# Sensor_PCB.net
KiCad netlist of a schematic drawn in EAGLE
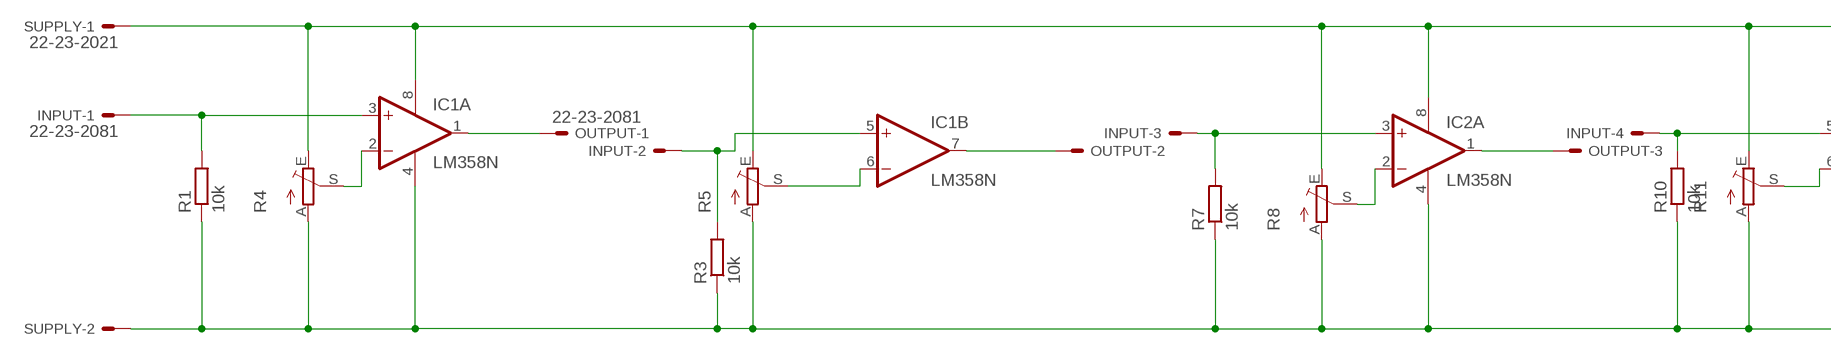
[diagram p0: schematic, sheet 1, part 1 of 2]
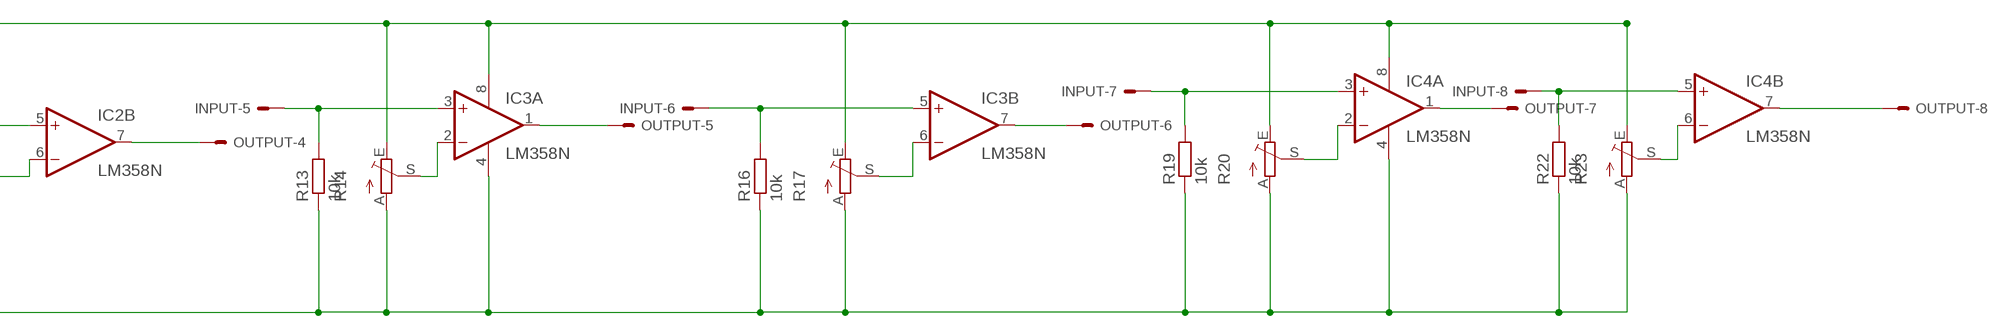
[diagram p1: schematic, sheet 1, part 2 of 2]

(export (version "E")
  (design (tool "Eeschema 10.0.6"))
  (components
    (comp (ref "IC1")
      (value "LM358N")
      (footprint "eagle-import:DIL08")
      (libsource (lib "eagle-import") (part "LM358N"))
    )
    (comp (ref "IC2")
      (value "LM358N")
      (footprint "eagle-import:DIL08")
      (libsource (lib "eagle-import") (part "LM358N"))
    )
    (comp (ref "IC3")
      (value "LM358N")
      (footprint "eagle-import:DIL08")
      (libsource (lib "eagle-import") (part "LM358N"))
    )
    (comp (ref "IC4")
      (value "LM358N")
      (footprint "eagle-import:DIL08")
      (libsource (lib "eagle-import") (part "LM358N"))
    )
    (comp (ref "INPUT")
      (value "22-23-2081")
      (footprint "eagle-import:22-23-2081")
      (fields (field (name "MF") "MOLEX"))
      (libsource (lib "eagle-import") (part "22-23-2081"))
    )
    (comp (ref "OUTPUT")
      (value "22-23-2081")
      (footprint "eagle-import:22-23-2081")
      (fields (field (name "MF") "MOLEX"))
      (libsource (lib "eagle-import") (part "22-23-2081"))
    )
    (comp (ref "R1")
      (value "10k")
      (footprint "eagle-import:R1206")
      (libsource (lib "eagle-import") (part "R-EU_R1206"))
    )
    (comp (ref "R3")
      (value "10k")
      (footprint "eagle-import:R1206")
      (libsource (lib "eagle-import") (part "R-EU_R1206"))
    )
    (comp (ref "R4")
      (value "TRIM_EU-S64Y")
      (footprint "eagle-import:S64Y")
      (libsource (lib "eagle-import") (part "TRIM_EU-S64Y"))
    )
    (comp (ref "R5")
      (value "TRIM_EU-S64Y")
      (footprint "eagle-import:S64Y")
      (libsource (lib "eagle-import") (part "TRIM_EU-S64Y"))
    )
    (comp (ref "R7")
      (value "10k")
      (footprint "eagle-import:R1206")
      (libsource (lib "eagle-import") (part "R-EU_R1206"))
    )
    (comp (ref "R8")
      (value "TRIM_EU-S64Y")
      (footprint "eagle-import:S64Y")
      (libsource (lib "eagle-import") (part "TRIM_EU-S64Y"))
    )
    (comp (ref "R10")
      (value "10k")
      (footprint "eagle-import:R1206")
      (libsource (lib "eagle-import") (part "R-EU_R1206"))
    )
    (comp (ref "R11")
      (value "TRIM_EU-S64Y")
      (footprint "eagle-import:S64Y")
      (libsource (lib "eagle-import") (part "TRIM_EU-S64Y"))
    )
    (comp (ref "R13")
      (value "10k")
      (footprint "eagle-import:R1206")
      (libsource (lib "eagle-import") (part "R-EU_R1206"))
    )
    (comp (ref "R14")
      (value "TRIM_EU-S64Y")
      (footprint "eagle-import:S64Y")
      (libsource (lib "eagle-import") (part "TRIM_EU-S64Y"))
    )
    (comp (ref "R16")
      (value "10k")
      (footprint "eagle-import:R1206")
      (libsource (lib "eagle-import") (part "R-EU_R1206"))
    )
    (comp (ref "R17")
      (value "TRIM_EU-S64Y")
      (footprint "eagle-import:S64Y")
      (libsource (lib "eagle-import") (part "TRIM_EU-S64Y"))
    )
    (comp (ref "R19")
      (value "10k")
      (footprint "eagle-import:R1206")
      (libsource (lib "eagle-import") (part "R-EU_R1206"))
    )
    (comp (ref "R20")
      (value "TRIM_EU-S64Y")
      (footprint "eagle-import:S64Y")
      (libsource (lib "eagle-import") (part "TRIM_EU-S64Y"))
    )
    (comp (ref "R22")
      (value "10k")
      (footprint "eagle-import:R1206")
      (libsource (lib "eagle-import") (part "R-EU_R1206"))
    )
    (comp (ref "R23")
      (value "TRIM_EU-S64Y")
      (footprint "eagle-import:S64Y")
      (libsource (lib "eagle-import") (part "TRIM_EU-S64Y"))
    )
    (comp (ref "SUPPLY")
      (value "22-23-2021")
      (footprint "eagle-import:22-23-2021")
      (fields (field (name "MF") "MOLEX"))
      (libsource (lib "eagle-import") (part "22-23-2021"))
    )
  )
  (nets
    (net (code "1") (name "Net-(IC1A-+IN)") (class "Default")
      (node (ref "IC1") (pin "3") (pinfunction "+IN_3") (pintype "input"))
      (node (ref "INPUT") (pin "1") (pinfunction "S_1") (pintype "passive"))
      (node (ref "R1") (pin "2") (pinfunction "2_2") (pintype "passive"))
    )
    (net (code "2") (name "Net-(IC1A--IN)") (class "Default")
      (node (ref "IC1") (pin "2") (pinfunction "-IN_2") (pintype "input"))
      (node (ref "R4") (pin "S") (pinfunction "S_S") (pintype "passive"))
    )
    (net (code "3") (name "Net-(IC1A-OUT)") (class "Default")
      (node (ref "IC1") (pin "1") (pinfunction "OUT_1") (pintype "output"))
      (node (ref "OUTPUT") (pin "1") (pinfunction "S_1") (pintype "passive"))
    )
    (net (code "4") (name "Net-(IC1B-+IN)") (class "Default")
      (node (ref "IC1") (pin "5") (pinfunction "+IN_5") (pintype "input"))
      (node (ref "INPUT") (pin "2") (pinfunction "S_2") (pintype "passive"))
      (node (ref "R3") (pin "2") (pinfunction "2_2") (pintype "passive"))
    )
    (net (code "5") (name "Net-(IC1B--IN)") (class "Default")
      (node (ref "IC1") (pin "6") (pinfunction "-IN_6") (pintype "input"))
      (node (ref "R5") (pin "S") (pinfunction "S_S") (pintype "passive"))
    )
    (net (code "6") (name "Net-(IC1B-OUT)") (class "Default")
      (node (ref "IC1") (pin "7") (pinfunction "OUT_7") (pintype "output"))
      (node (ref "OUTPUT") (pin "2") (pinfunction "S_2") (pintype "passive"))
    )
    (net (code "7") (name "Net-(IC1C-V+)") (class "Default")
      (node (ref "IC1") (pin "8") (pinfunction "V+_8") (pintype "power_in"))
      (node (ref "IC2") (pin "8") (pinfunction "V+_8") (pintype "power_in"))
      (node (ref "IC3") (pin "8") (pinfunction "V+_8") (pintype "power_in"))
      (node (ref "IC4") (pin "8") (pinfunction "V+_8") (pintype "power_in"))
      (node (ref "R11") (pin "E") (pinfunction "E_E") (pintype "passive"))
      (node (ref "R14") (pin "E") (pinfunction "E_E") (pintype "passive"))
      (node (ref "R17") (pin "E") (pinfunction "E_E") (pintype "passive"))
      (node (ref "R20") (pin "E") (pinfunction "E_E") (pintype "passive"))
      (node (ref "R23") (pin "E") (pinfunction "E_E") (pintype "passive"))
      (node (ref "R4") (pin "E") (pinfunction "E_E") (pintype "passive"))
      (node (ref "R5") (pin "E") (pinfunction "E_E") (pintype "passive"))
      (node (ref "R8") (pin "E") (pinfunction "E_E") (pintype "passive"))
      (node (ref "SUPPLY") (pin "1") (pinfunction "S_1") (pintype "passive"))
    )
    (net (code "8") (name "Net-(IC1C-V-)") (class "Default")
      (node (ref "IC1") (pin "4") (pinfunction "V-_4") (pintype "power_in"))
      (node (ref "IC2") (pin "4") (pinfunction "V-_4") (pintype "power_in"))
      (node (ref "IC3") (pin "4") (pinfunction "V-_4") (pintype "power_in"))
      (node (ref "IC4") (pin "4") (pinfunction "V-_4") (pintype "power_in"))
      (node (ref "R1") (pin "1") (pinfunction "1_1") (pintype "passive"))
      (node (ref "R10") (pin "1") (pinfunction "1_1") (pintype "passive"))
      (node (ref "R11") (pin "A") (pinfunction "A_A") (pintype "passive"))
      (node (ref "R13") (pin "1") (pinfunction "1_1") (pintype "passive"))
      (node (ref "R14") (pin "A") (pinfunction "A_A") (pintype "passive"))
      (node (ref "R16") (pin "1") (pinfunction "1_1") (pintype "passive"))
      (node (ref "R17") (pin "A") (pinfunction "A_A") (pintype "passive"))
      (node (ref "R19") (pin "1") (pinfunction "1_1") (pintype "passive"))
      (node (ref "R20") (pin "A") (pinfunction "A_A") (pintype "passive"))
      (node (ref "R22") (pin "1") (pinfunction "1_1") (pintype "passive"))
      (node (ref "R23") (pin "A") (pinfunction "A_A") (pintype "passive"))
      (node (ref "R3") (pin "1") (pinfunction "1_1") (pintype "passive"))
      (node (ref "R4") (pin "A") (pinfunction "A_A") (pintype "passive"))
      (node (ref "R5") (pin "A") (pinfunction "A_A") (pintype "passive"))
      (node (ref "R7") (pin "1") (pinfunction "1_1") (pintype "passive"))
      (node (ref "R8") (pin "A") (pinfunction "A_A") (pintype "passive"))
      (node (ref "SUPPLY") (pin "2") (pinfunction "S_2") (pintype "passive"))
    )
    (net (code "9") (name "Net-(IC2A-+IN)") (class "Default")
      (node (ref "IC2") (pin "3") (pinfunction "+IN_3") (pintype "input"))
      (node (ref "INPUT") (pin "3") (pinfunction "S_3") (pintype "passive"))
      (node (ref "R7") (pin "2") (pinfunction "2_2") (pintype "passive"))
    )
    (net (code "10") (name "Net-(IC2A--IN)") (class "Default")
      (node (ref "IC2") (pin "2") (pinfunction "-IN_2") (pintype "input"))
      (node (ref "R8") (pin "S") (pinfunction "S_S") (pintype "passive"))
    )
    (net (code "11") (name "Net-(IC2A-OUT)") (class "Default")
      (node (ref "IC2") (pin "1") (pinfunction "OUT_1") (pintype "output"))
      (node (ref "OUTPUT") (pin "3") (pinfunction "S_3") (pintype "passive"))
    )
    (net (code "12") (name "Net-(IC2B-+IN)") (class "Default")
      (node (ref "IC2") (pin "5") (pinfunction "+IN_5") (pintype "input"))
      (node (ref "INPUT") (pin "4") (pinfunction "S_4") (pintype "passive"))
      (node (ref "R10") (pin "2") (pinfunction "2_2") (pintype "passive"))
    )
    (net (code "13") (name "Net-(IC2B--IN)") (class "Default")
      (node (ref "IC2") (pin "6") (pinfunction "-IN_6") (pintype "input"))
      (node (ref "R11") (pin "S") (pinfunction "S_S") (pintype "passive"))
    )
    (net (code "14") (name "Net-(IC2B-OUT)") (class "Default")
      (node (ref "IC2") (pin "7") (pinfunction "OUT_7") (pintype "output"))
      (node (ref "OUTPUT") (pin "4") (pinfunction "S_4") (pintype "passive"))
    )
    (net (code "15") (name "Net-(IC3A-+IN)") (class "Default")
      (node (ref "IC3") (pin "3") (pinfunction "+IN_3") (pintype "input"))
      (node (ref "INPUT") (pin "5") (pinfunction "S_5") (pintype "passive"))
      (node (ref "R13") (pin "2") (pinfunction "2_2") (pintype "passive"))
    )
    (net (code "16") (name "Net-(IC3A--IN)") (class "Default")
      (node (ref "IC3") (pin "2") (pinfunction "-IN_2") (pintype "input"))
      (node (ref "R14") (pin "S") (pinfunction "S_S") (pintype "passive"))
    )
    (net (code "17") (name "Net-(IC3A-OUT)") (class "Default")
      (node (ref "IC3") (pin "1") (pinfunction "OUT_1") (pintype "output"))
      (node (ref "OUTPUT") (pin "5") (pinfunction "S_5") (pintype "passive"))
    )
    (net (code "18") (name "Net-(IC3B-+IN)") (class "Default")
      (node (ref "IC3") (pin "5") (pinfunction "+IN_5") (pintype "input"))
      (node (ref "INPUT") (pin "6") (pinfunction "S_6") (pintype "passive"))
      (node (ref "R16") (pin "2") (pinfunction "2_2") (pintype "passive"))
    )
    (net (code "19") (name "Net-(IC3B--IN)") (class "Default")
      (node (ref "IC3") (pin "6") (pinfunction "-IN_6") (pintype "input"))
      (node (ref "R17") (pin "S") (pinfunction "S_S") (pintype "passive"))
    )
    (net (code "20") (name "Net-(IC3B-OUT)") (class "Default")
      (node (ref "IC3") (pin "7") (pinfunction "OUT_7") (pintype "output"))
      (node (ref "OUTPUT") (pin "6") (pinfunction "S_6") (pintype "passive"))
    )
    (net (code "21") (name "Net-(IC4A-+IN)") (class "Default")
      (node (ref "IC4") (pin "3") (pinfunction "+IN_3") (pintype "input"))
      (node (ref "INPUT") (pin "7") (pinfunction "S_7") (pintype "passive"))
      (node (ref "R19") (pin "2") (pinfunction "2_2") (pintype "passive"))
    )
    (net (code "22") (name "Net-(IC4A--IN)") (class "Default")
      (node (ref "IC4") (pin "2") (pinfunction "-IN_2") (pintype "input"))
      (node (ref "R20") (pin "S") (pinfunction "S_S") (pintype "passive"))
    )
    (net (code "23") (name "Net-(IC4A-OUT)") (class "Default")
      (node (ref "IC4") (pin "1") (pinfunction "OUT_1") (pintype "output"))
      (node (ref "OUTPUT") (pin "7") (pinfunction "S_7") (pintype "passive"))
    )
    (net (code "24") (name "Net-(IC4B-+IN)") (class "Default")
      (node (ref "IC4") (pin "5") (pinfunction "+IN_5") (pintype "input"))
      (node (ref "INPUT") (pin "8") (pinfunction "S_8") (pintype "passive"))
      (node (ref "R22") (pin "2") (pinfunction "2_2") (pintype "passive"))
    )
    (net (code "25") (name "Net-(IC4B--IN)") (class "Default")
      (node (ref "IC4") (pin "6") (pinfunction "-IN_6") (pintype "input"))
      (node (ref "R23") (pin "S") (pinfunction "S_S") (pintype "passive"))
    )
    (net (code "26") (name "Net-(IC4B-OUT)") (class "Default")
      (node (ref "IC4") (pin "7") (pinfunction "OUT_7") (pintype "output"))
      (node (ref "OUTPUT") (pin "8") (pinfunction "S_8") (pintype "passive"))
    )
  )
)
